# EEG_4.net
KiCad netlist of a schematic drawn in Altium Designer
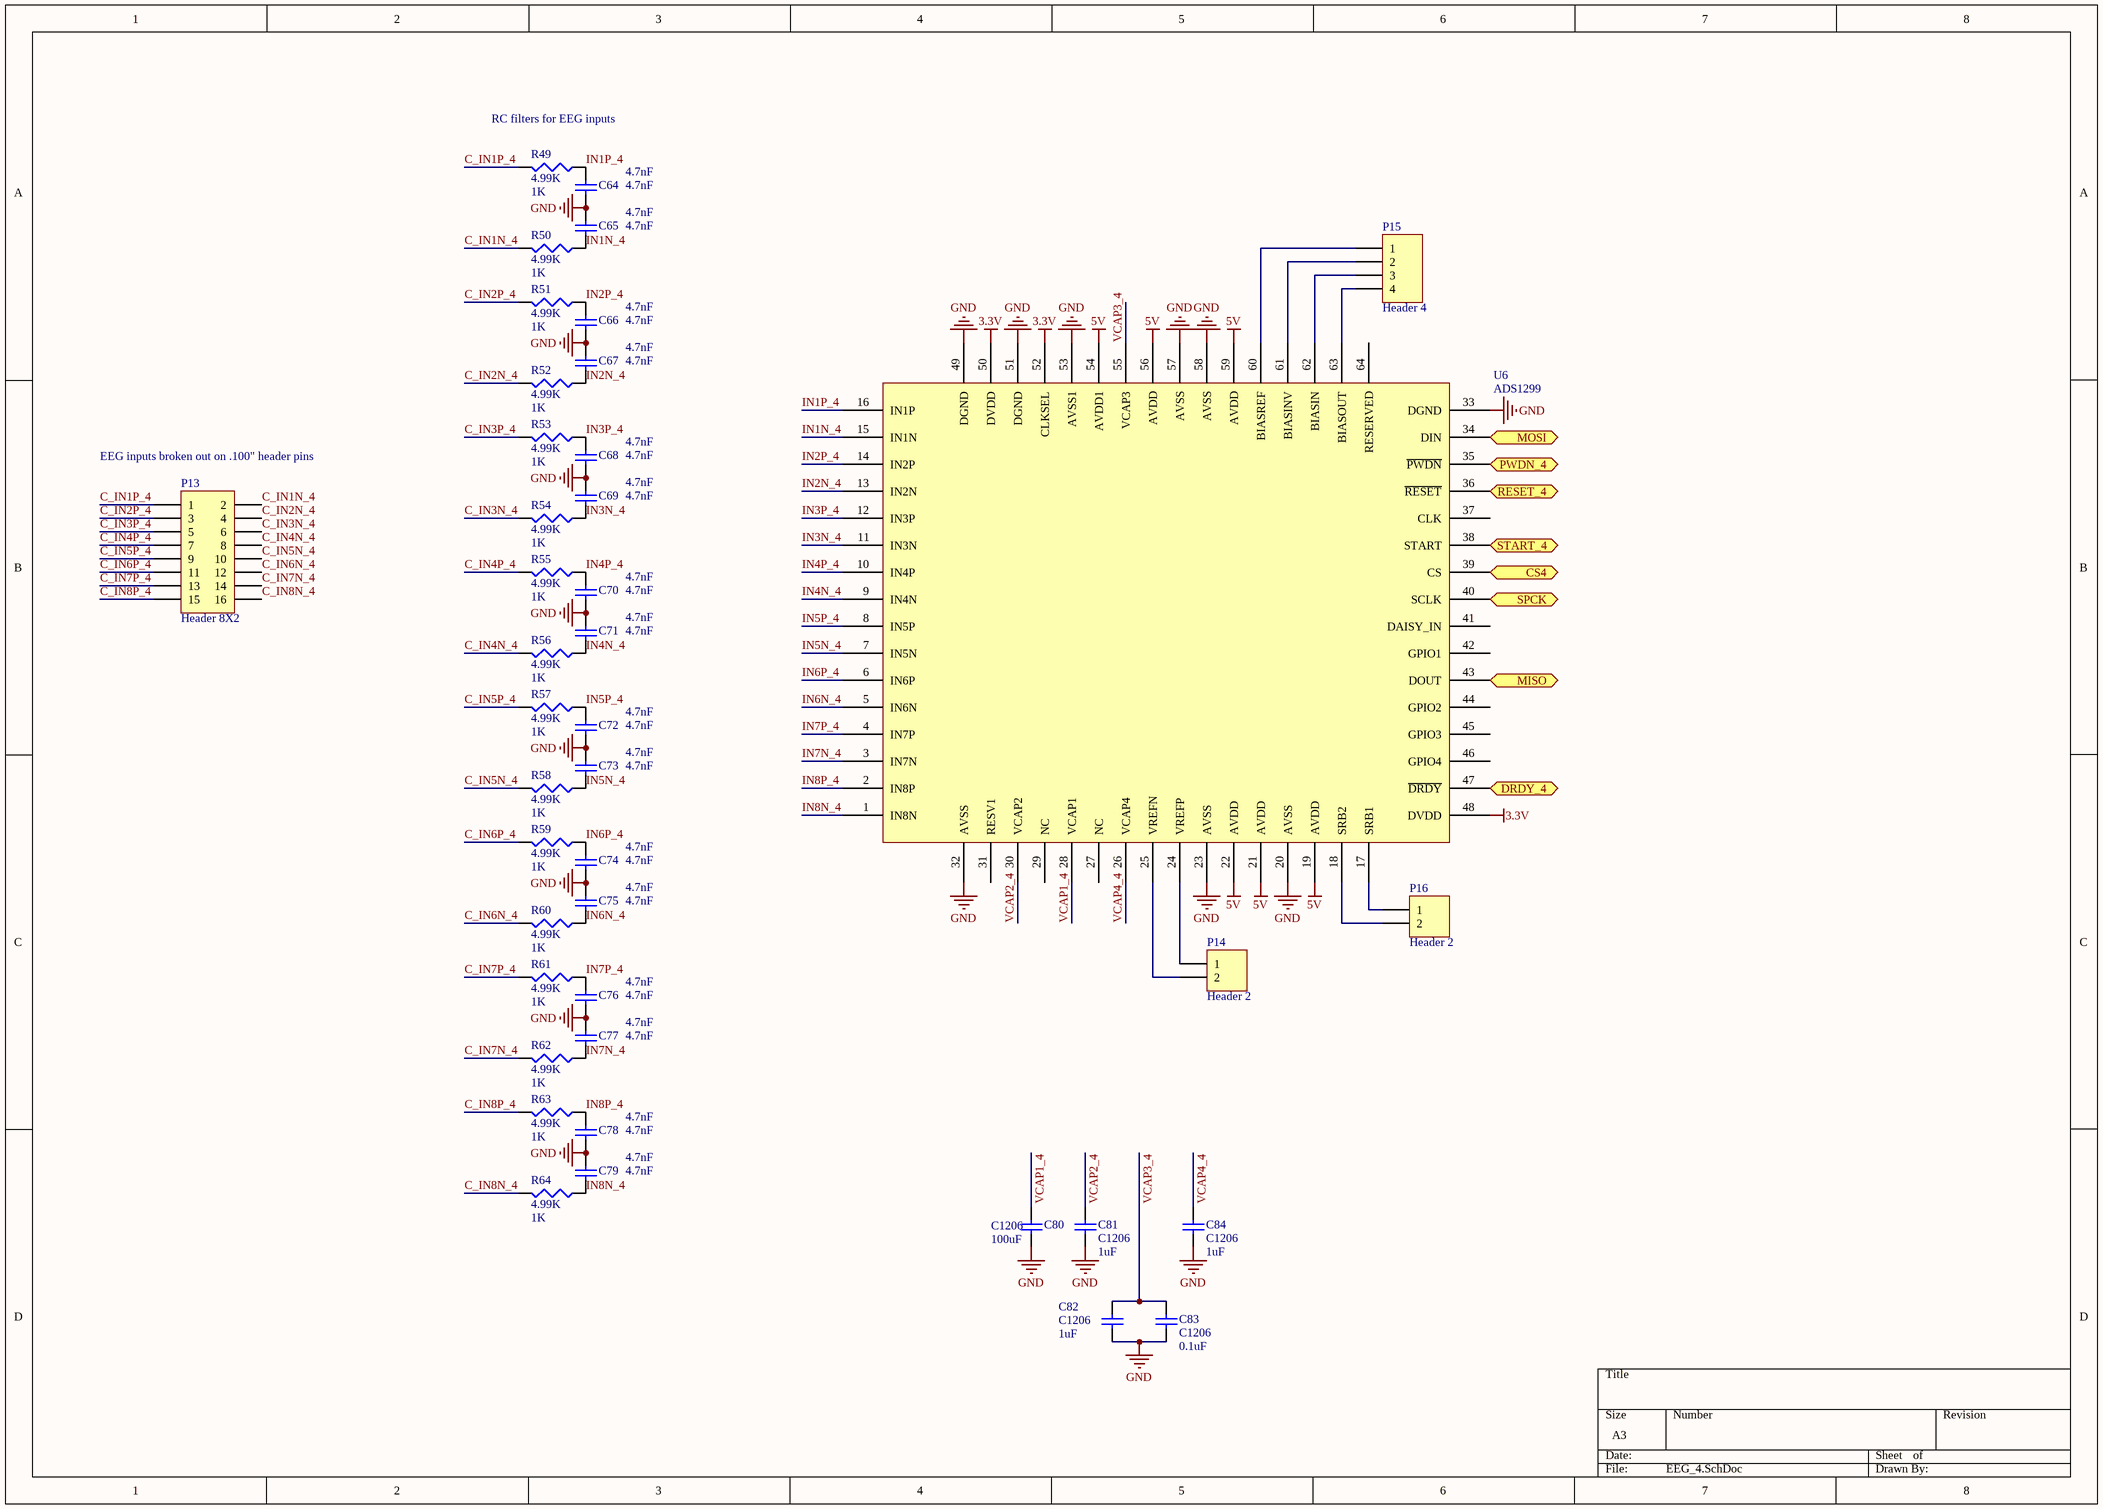
[diagram p0: EEG_4.SchDoc]

(export (version "E")
  (design (tool "Eeschema 10.0.6"))
  (components
    (comp (ref "C64")
      (value "4.7nF")
      (footprint "1608[0603]")
      (description "Capacitor (Semiconductor SIM Model)")
      (fields (field (name "ALTIUM_VALUE") "4.7nF") (field (name "PUBLISHER") "Altium Limited"))
      (libsource (lib "Miscellaneous Devices") (part "Cap Semi"))
    )
    (comp (ref "C65")
      (value "4.7nF")
      (footprint "1608[0603]")
      (description "Capacitor (Semiconductor SIM Model)")
      (fields (field (name "ALTIUM_VALUE") "4.7nF") (field (name "PUBLISHER") "Altium Limited"))
      (libsource (lib "Miscellaneous Devices") (part "Cap Semi"))
    )
    (comp (ref "C66")
      (value "4.7nF")
      (footprint "1608[0603]")
      (description "Capacitor (Semiconductor SIM Model)")
      (fields (field (name "ALTIUM_VALUE") "4.7nF") (field (name "PUBLISHER") "Altium Limited"))
      (libsource (lib "Miscellaneous Devices") (part "Cap Semi"))
    )
    (comp (ref "C67")
      (value "4.7nF")
      (footprint "1608[0603]")
      (description "Capacitor (Semiconductor SIM Model)")
      (fields (field (name "ALTIUM_VALUE") "4.7nF") (field (name "PUBLISHER") "Altium Limited"))
      (libsource (lib "Miscellaneous Devices") (part "Cap Semi"))
    )
    (comp (ref "C68")
      (value "4.7nF")
      (footprint "1608[0603]")
      (description "Capacitor (Semiconductor SIM Model)")
      (fields (field (name "ALTIUM_VALUE") "4.7nF") (field (name "PUBLISHER") "Altium Limited"))
      (libsource (lib "Miscellaneous Devices") (part "Cap Semi"))
    )
    (comp (ref "C69")
      (value "4.7nF")
      (footprint "1608[0603]")
      (description "Capacitor (Semiconductor SIM Model)")
      (fields (field (name "ALTIUM_VALUE") "4.7nF") (field (name "PUBLISHER") "Altium Limited"))
      (libsource (lib "Miscellaneous Devices") (part "Cap Semi"))
    )
    (comp (ref "C70")
      (value "4.7nF")
      (footprint "1608[0603]")
      (description "Capacitor (Semiconductor SIM Model)")
      (fields (field (name "ALTIUM_VALUE") "4.7nF") (field (name "PUBLISHER") "Altium Limited"))
      (libsource (lib "Miscellaneous Devices") (part "Cap Semi"))
    )
    (comp (ref "C71")
      (value "4.7nF")
      (footprint "1608[0603]")
      (description "Capacitor (Semiconductor SIM Model)")
      (fields (field (name "ALTIUM_VALUE") "4.7nF") (field (name "PUBLISHER") "Altium Limited"))
      (libsource (lib "Miscellaneous Devices") (part "Cap Semi"))
    )
    (comp (ref "C72")
      (value "4.7nF")
      (footprint "1608[0603]")
      (description "Capacitor (Semiconductor SIM Model)")
      (fields (field (name "ALTIUM_VALUE") "4.7nF") (field (name "PUBLISHER") "Altium Limited"))
      (libsource (lib "Miscellaneous Devices") (part "Cap Semi"))
    )
    (comp (ref "C73")
      (value "4.7nF")
      (footprint "1608[0603]")
      (description "Capacitor (Semiconductor SIM Model)")
      (fields (field (name "ALTIUM_VALUE") "4.7nF") (field (name "PUBLISHER") "Altium Limited"))
      (libsource (lib "Miscellaneous Devices") (part "Cap Semi"))
    )
    (comp (ref "C74")
      (value "4.7nF")
      (footprint "1608[0603]")
      (description "Capacitor (Semiconductor SIM Model)")
      (fields (field (name "ALTIUM_VALUE") "4.7nF") (field (name "PUBLISHER") "Altium Limited"))
      (libsource (lib "Miscellaneous Devices") (part "Cap Semi"))
    )
    (comp (ref "C75")
      (value "4.7nF")
      (footprint "1608[0603]")
      (description "Capacitor (Semiconductor SIM Model)")
      (fields (field (name "ALTIUM_VALUE") "4.7nF") (field (name "PUBLISHER") "Altium Limited"))
      (libsource (lib "Miscellaneous Devices") (part "Cap Semi"))
    )
    (comp (ref "C76")
      (value "4.7nF")
      (footprint "1608[0603]")
      (description "Capacitor (Semiconductor SIM Model)")
      (fields (field (name "ALTIUM_VALUE") "4.7nF") (field (name "PUBLISHER") "Altium Limited"))
      (libsource (lib "Miscellaneous Devices") (part "Cap Semi"))
    )
    (comp (ref "C77")
      (value "4.7nF")
      (footprint "1608[0603]")
      (description "Capacitor (Semiconductor SIM Model)")
      (fields (field (name "ALTIUM_VALUE") "4.7nF") (field (name "PUBLISHER") "Altium Limited"))
      (libsource (lib "Miscellaneous Devices") (part "Cap Semi"))
    )
    (comp (ref "C78")
      (value "4.7nF")
      (footprint "1608[0603]")
      (description "Capacitor (Semiconductor SIM Model)")
      (fields (field (name "ALTIUM_VALUE") "4.7nF") (field (name "PUBLISHER") "Altium Limited"))
      (libsource (lib "Miscellaneous Devices") (part "Cap Semi"))
    )
    (comp (ref "C79")
      (value "4.7nF")
      (footprint "1608[0603]")
      (description "Capacitor (Semiconductor SIM Model)")
      (fields (field (name "ALTIUM_VALUE") "4.7nF") (field (name "PUBLISHER") "Altium Limited"))
      (libsource (lib "Miscellaneous Devices") (part "Cap Semi"))
    )
    (comp (ref "C80")
      (value "C1206")
      (footprint "1608[0603]")
      (description "Capacitor (Semiconductor SIM Model)")
      (fields (field (name "ALTIUM_VALUE") "100uF") (field (name "PUBLISHER") "Altium Limited"))
      (libsource (lib "Miscellaneous Devices") (part "Cap Semi"))
    )
    (comp (ref "C81")
      (value "C1206")
      (footprint "1608[0603]")
      (description "Capacitor (Semiconductor SIM Model)")
      (fields (field (name "ALTIUM_VALUE") "1uF") (field (name "PUBLISHER") "Altium Limited"))
      (libsource (lib "Miscellaneous Devices") (part "Cap Semi"))
    )
    (comp (ref "C82")
      (value "C1206")
      (footprint "1608[0603]")
      (description "Capacitor (Semiconductor SIM Model)")
      (fields (field (name "ALTIUM_VALUE") "1uF") (field (name "PUBLISHER") "Altium Limited"))
      (libsource (lib "Miscellaneous Devices") (part "Cap Semi"))
    )
    (comp (ref "C83")
      (value "C1206")
      (footprint "1608[0603]")
      (description "Capacitor (Semiconductor SIM Model)")
      (fields (field (name "ALTIUM_VALUE") "0.1uF") (field (name "PUBLISHER") "Altium Limited"))
      (libsource (lib "Miscellaneous Devices") (part "Cap Semi"))
    )
    (comp (ref "C84")
      (value "C1206")
      (footprint "1608[0603]")
      (description "Capacitor (Semiconductor SIM Model)")
      (fields (field (name "ALTIUM_VALUE") "1uF") (field (name "PUBLISHER") "Altium Limited"))
      (libsource (lib "Miscellaneous Devices") (part "Cap Semi"))
    )
    (comp (ref "P13")
      (value "Header 8X2")
      (footprint "HDR2X8")
      (description "Header, 8-Pin, Dual row")
      (fields (field (name "PUBLISHER") "Altium Limited"))
      (libsource (lib "Miscellaneous Connectors") (part "Header 8X2"))
    )
    (comp (ref "P14")
      (value "Header 2")
      (footprint "HDR1X2")
      (description "Header, 2-Pin")
      (fields (field (name "PUBLISHER") "Altium Limited"))
      (libsource (lib "Miscellaneous Connectors") (part "Header 2"))
    )
    (comp (ref "P15")
      (value "Header 4")
      (footprint "HDR1X4")
      (description "Header, 4-Pin")
      (fields (field (name "PUBLISHER") "Altium Limited"))
      (libsource (lib "Miscellaneous Connectors") (part "Header 4"))
    )
    (comp (ref "P16")
      (value "Header 2")
      (footprint "HDR1X2")
      (description "Header, 2-Pin")
      (fields (field (name "PUBLISHER") "Altium Limited"))
      (libsource (lib "Miscellaneous Connectors") (part "Header 2"))
    )
    (comp (ref "R49")
      (value "4.99K")
      (footprint "1608[0603]")
      (description "Resistor")
      (fields (field (name "ALTIUM_VALUE") "1K") (field (name "PUBLISHER") "Altium Limited"))
      (libsource (lib "Miscellaneous Devices") (part "Res3"))
    )
    (comp (ref "R50")
      (value "4.99K")
      (footprint "1608[0603]")
      (description "Resistor")
      (fields (field (name "ALTIUM_VALUE") "1K") (field (name "PUBLISHER") "Altium Limited"))
      (libsource (lib "Miscellaneous Devices") (part "Res3"))
    )
    (comp (ref "R51")
      (value "4.99K")
      (footprint "1608[0603]")
      (description "Resistor")
      (fields (field (name "ALTIUM_VALUE") "1K") (field (name "PUBLISHER") "Altium Limited"))
      (libsource (lib "Miscellaneous Devices") (part "Res3"))
    )
    (comp (ref "R52")
      (value "4.99K")
      (footprint "1608[0603]")
      (description "Resistor")
      (fields (field (name "ALTIUM_VALUE") "1K") (field (name "PUBLISHER") "Altium Limited"))
      (libsource (lib "Miscellaneous Devices") (part "Res3"))
    )
    (comp (ref "R53")
      (value "4.99K")
      (footprint "1608[0603]")
      (description "Resistor")
      (fields (field (name "ALTIUM_VALUE") "1K") (field (name "PUBLISHER") "Altium Limited"))
      (libsource (lib "Miscellaneous Devices") (part "Res3"))
    )
    (comp (ref "R54")
      (value "4.99K")
      (footprint "1608[0603]")
      (description "Resistor")
      (fields (field (name "ALTIUM_VALUE") "1K") (field (name "PUBLISHER") "Altium Limited"))
      (libsource (lib "Miscellaneous Devices") (part "Res3"))
    )
    (comp (ref "R55")
      (value "4.99K")
      (footprint "1608[0603]")
      (description "Resistor")
      (fields (field (name "ALTIUM_VALUE") "1K") (field (name "PUBLISHER") "Altium Limited"))
      (libsource (lib "Miscellaneous Devices") (part "Res3"))
    )
    (comp (ref "R56")
      (value "4.99K")
      (footprint "1608[0603]")
      (description "Resistor")
      (fields (field (name "ALTIUM_VALUE") "1K") (field (name "PUBLISHER") "Altium Limited"))
      (libsource (lib "Miscellaneous Devices") (part "Res3"))
    )
    (comp (ref "R57")
      (value "4.99K")
      (footprint "1608[0603]")
      (description "Resistor")
      (fields (field (name "ALTIUM_VALUE") "1K") (field (name "PUBLISHER") "Altium Limited"))
      (libsource (lib "Miscellaneous Devices") (part "Res3"))
    )
    (comp (ref "R58")
      (value "4.99K")
      (footprint "1608[0603]")
      (description "Resistor")
      (fields (field (name "ALTIUM_VALUE") "1K") (field (name "PUBLISHER") "Altium Limited"))
      (libsource (lib "Miscellaneous Devices") (part "Res3"))
    )
    (comp (ref "R59")
      (value "4.99K")
      (footprint "1608[0603]")
      (description "Resistor")
      (fields (field (name "ALTIUM_VALUE") "1K") (field (name "PUBLISHER") "Altium Limited"))
      (libsource (lib "Miscellaneous Devices") (part "Res3"))
    )
    (comp (ref "R60")
      (value "4.99K")
      (footprint "1608[0603]")
      (description "Resistor")
      (fields (field (name "ALTIUM_VALUE") "1K") (field (name "PUBLISHER") "Altium Limited"))
      (libsource (lib "Miscellaneous Devices") (part "Res3"))
    )
    (comp (ref "R61")
      (value "4.99K")
      (footprint "1608[0603]")
      (description "Resistor")
      (fields (field (name "ALTIUM_VALUE") "1K") (field (name "PUBLISHER") "Altium Limited"))
      (libsource (lib "Miscellaneous Devices") (part "Res3"))
    )
    (comp (ref "R62")
      (value "4.99K")
      (footprint "1608[0603]")
      (description "Resistor")
      (fields (field (name "ALTIUM_VALUE") "1K") (field (name "PUBLISHER") "Altium Limited"))
      (libsource (lib "Miscellaneous Devices") (part "Res3"))
    )
    (comp (ref "R63")
      (value "4.99K")
      (footprint "1608[0603]")
      (description "Resistor")
      (fields (field (name "ALTIUM_VALUE") "1K") (field (name "PUBLISHER") "Altium Limited"))
      (libsource (lib "Miscellaneous Devices") (part "Res3"))
    )
    (comp (ref "R64")
      (value "4.99K")
      (footprint "1608[0603]")
      (description "Resistor")
      (fields (field (name "ALTIUM_VALUE") "1K") (field (name "PUBLISHER") "Altium Limited"))
      (libsource (lib "Miscellaneous Devices") (part "Res3"))
    )
    (comp (ref "U6")
      (value "ADS1299")
      (footprint "ADS1299 Plastic QFP")
      (libsource (lib "ADS1299") (part "ADS1299"))
    )
  )
  (nets
    (net (code "1") (name "/CS4") (class "Default")
      (node (ref "U6") (pin "39") (pinfunction "CS_39") (pintype "passive"))
    )
    (net (code "2") (name "/C_IN1N_4") (class "Default")
      (node (ref "P13") (pin "2") (pinfunction "2_2") (pintype "passive"))
      (node (ref "R50") (pin "2") (pinfunction "2_2") (pintype "passive"))
    )
    (net (code "3") (name "/C_IN1P_4") (class "Default")
      (node (ref "P13") (pin "1") (pinfunction "1_1") (pintype "passive"))
      (node (ref "R49") (pin "2") (pinfunction "2_2") (pintype "passive"))
    )
    (net (code "4") (name "/C_IN2N_4") (class "Default")
      (node (ref "P13") (pin "4") (pinfunction "4_4") (pintype "passive"))
      (node (ref "R52") (pin "2") (pinfunction "2_2") (pintype "passive"))
    )
    (net (code "5") (name "/C_IN2P_4") (class "Default")
      (node (ref "P13") (pin "3") (pinfunction "3_3") (pintype "passive"))
      (node (ref "R51") (pin "2") (pinfunction "2_2") (pintype "passive"))
    )
    (net (code "6") (name "/C_IN3N_4") (class "Default")
      (node (ref "P13") (pin "6") (pinfunction "6_6") (pintype "passive"))
      (node (ref "R54") (pin "2") (pinfunction "2_2") (pintype "passive"))
    )
    (net (code "7") (name "/C_IN3P_4") (class "Default")
      (node (ref "P13") (pin "5") (pinfunction "5_5") (pintype "passive"))
      (node (ref "R53") (pin "2") (pinfunction "2_2") (pintype "passive"))
    )
    (net (code "8") (name "/C_IN4N_4") (class "Default")
      (node (ref "P13") (pin "8") (pinfunction "8_8") (pintype "passive"))
      (node (ref "R56") (pin "2") (pinfunction "2_2") (pintype "passive"))
    )
    (net (code "9") (name "/C_IN4P_4") (class "Default")
      (node (ref "P13") (pin "7") (pinfunction "7_7") (pintype "passive"))
      (node (ref "R55") (pin "2") (pinfunction "2_2") (pintype "passive"))
    )
    (net (code "10") (name "/C_IN5N_4") (class "Default")
      (node (ref "P13") (pin "10") (pinfunction "10_10") (pintype "passive"))
      (node (ref "R58") (pin "2") (pinfunction "2_2") (pintype "passive"))
    )
    (net (code "11") (name "/C_IN5P_4") (class "Default")
      (node (ref "P13") (pin "9") (pinfunction "9_9") (pintype "passive"))
      (node (ref "R57") (pin "2") (pinfunction "2_2") (pintype "passive"))
    )
    (net (code "12") (name "/C_IN6N_4") (class "Default")
      (node (ref "P13") (pin "12") (pinfunction "12_12") (pintype "passive"))
      (node (ref "R60") (pin "2") (pinfunction "2_2") (pintype "passive"))
    )
    (net (code "13") (name "/C_IN6P_4") (class "Default")
      (node (ref "P13") (pin "11") (pinfunction "11_11") (pintype "passive"))
      (node (ref "R59") (pin "2") (pinfunction "2_2") (pintype "passive"))
    )
    (net (code "14") (name "/C_IN7N_4") (class "Default")
      (node (ref "P13") (pin "14") (pinfunction "14_14") (pintype "passive"))
      (node (ref "R62") (pin "2") (pinfunction "2_2") (pintype "passive"))
    )
    (net (code "15") (name "/C_IN7P_4") (class "Default")
      (node (ref "P13") (pin "13") (pinfunction "13_13") (pintype "passive"))
      (node (ref "R61") (pin "2") (pinfunction "2_2") (pintype "passive"))
    )
    (net (code "16") (name "/C_IN8N_4") (class "Default")
      (node (ref "P13") (pin "16") (pinfunction "16_16") (pintype "passive"))
      (node (ref "R64") (pin "2") (pinfunction "2_2") (pintype "passive"))
    )
    (net (code "17") (name "/C_IN8P_4") (class "Default")
      (node (ref "P13") (pin "15") (pinfunction "15_15") (pintype "passive"))
      (node (ref "R63") (pin "2") (pinfunction "2_2") (pintype "passive"))
    )
    (net (code "18") (name "/DRDY_4") (class "Default")
      (node (ref "U6") (pin "47") (pinfunction "~{DRDY}_47") (pintype "passive"))
    )
    (net (code "19") (name "/IN1N_4") (class "Default")
      (node (ref "C65") (pin "1") (pinfunction "1_1") (pintype "passive"))
      (node (ref "R50") (pin "1") (pinfunction "1_1") (pintype "passive"))
      (node (ref "U6") (pin "15") (pinfunction "IN1N_15") (pintype "passive"))
    )
    (net (code "20") (name "/IN1P_4") (class "Default")
      (node (ref "C64") (pin "2") (pinfunction "2_2") (pintype "passive"))
      (node (ref "R49") (pin "1") (pinfunction "1_1") (pintype "passive"))
      (node (ref "U6") (pin "16") (pinfunction "IN1P_16") (pintype "passive"))
    )
    (net (code "21") (name "/IN2N_4") (class "Default")
      (node (ref "C67") (pin "1") (pinfunction "1_1") (pintype "passive"))
      (node (ref "R52") (pin "1") (pinfunction "1_1") (pintype "passive"))
      (node (ref "U6") (pin "13") (pinfunction "IN2N_13") (pintype "passive"))
    )
    (net (code "22") (name "/IN2P_4") (class "Default")
      (node (ref "C66") (pin "2") (pinfunction "2_2") (pintype "passive"))
      (node (ref "R51") (pin "1") (pinfunction "1_1") (pintype "passive"))
      (node (ref "U6") (pin "14") (pinfunction "IN2P_14") (pintype "passive"))
    )
    (net (code "23") (name "/IN3N_4") (class "Default")
      (node (ref "C69") (pin "1") (pinfunction "1_1") (pintype "passive"))
      (node (ref "R54") (pin "1") (pinfunction "1_1") (pintype "passive"))
      (node (ref "U6") (pin "11") (pinfunction "IN3N_11") (pintype "passive"))
    )
    (net (code "24") (name "/IN3P_4") (class "Default")
      (node (ref "C68") (pin "2") (pinfunction "2_2") (pintype "passive"))
      (node (ref "R53") (pin "1") (pinfunction "1_1") (pintype "passive"))
      (node (ref "U6") (pin "12") (pinfunction "IN3P_12") (pintype "passive"))
    )
    (net (code "25") (name "/IN4N_4") (class "Default")
      (node (ref "C71") (pin "1") (pinfunction "1_1") (pintype "passive"))
      (node (ref "R56") (pin "1") (pinfunction "1_1") (pintype "passive"))
      (node (ref "U6") (pin "9") (pinfunction "IN4N_9") (pintype "passive"))
    )
    (net (code "26") (name "/IN4P_4") (class "Default")
      (node (ref "C70") (pin "2") (pinfunction "2_2") (pintype "passive"))
      (node (ref "R55") (pin "1") (pinfunction "1_1") (pintype "passive"))
      (node (ref "U6") (pin "10") (pinfunction "IN4P_10") (pintype "passive"))
    )
    (net (code "27") (name "/IN5N_4") (class "Default")
      (node (ref "C73") (pin "1") (pinfunction "1_1") (pintype "passive"))
      (node (ref "R58") (pin "1") (pinfunction "1_1") (pintype "passive"))
      (node (ref "U6") (pin "7") (pinfunction "IN5N_7") (pintype "passive"))
    )
    (net (code "28") (name "/IN5P_4") (class "Default")
      (node (ref "C72") (pin "2") (pinfunction "2_2") (pintype "passive"))
      (node (ref "R57") (pin "1") (pinfunction "1_1") (pintype "passive"))
      (node (ref "U6") (pin "8") (pinfunction "IN5P_8") (pintype "passive"))
    )
    (net (code "29") (name "/IN6N_4") (class "Default")
      (node (ref "C75") (pin "1") (pinfunction "1_1") (pintype "passive"))
      (node (ref "R60") (pin "1") (pinfunction "1_1") (pintype "passive"))
      (node (ref "U6") (pin "5") (pinfunction "IN6N_5") (pintype "passive"))
    )
    (net (code "30") (name "/IN6P_4") (class "Default")
      (node (ref "C74") (pin "2") (pinfunction "2_2") (pintype "passive"))
      (node (ref "R59") (pin "1") (pinfunction "1_1") (pintype "passive"))
      (node (ref "U6") (pin "6") (pinfunction "IN6P_6") (pintype "passive"))
    )
    (net (code "31") (name "/IN7N_4") (class "Default")
      (node (ref "C77") (pin "1") (pinfunction "1_1") (pintype "passive"))
      (node (ref "R62") (pin "1") (pinfunction "1_1") (pintype "passive"))
      (node (ref "U6") (pin "3") (pinfunction "IN7N_3") (pintype "passive"))
    )
    (net (code "32") (name "/IN7P_4") (class "Default")
      (node (ref "C76") (pin "2") (pinfunction "2_2") (pintype "passive"))
      (node (ref "R61") (pin "1") (pinfunction "1_1") (pintype "passive"))
      (node (ref "U6") (pin "4") (pinfunction "IN7P_4") (pintype "passive"))
    )
    (net (code "33") (name "/IN8N_4") (class "Default")
      (node (ref "C79") (pin "1") (pinfunction "1_1") (pintype "passive"))
      (node (ref "R64") (pin "1") (pinfunction "1_1") (pintype "passive"))
      (node (ref "U6") (pin "1") (pinfunction "IN8N_1") (pintype "passive"))
    )
    (net (code "34") (name "/IN8P_4") (class "Default")
      (node (ref "C78") (pin "2") (pinfunction "2_2") (pintype "passive"))
      (node (ref "R63") (pin "1") (pinfunction "1_1") (pintype "passive"))
      (node (ref "U6") (pin "2") (pinfunction "IN8P_2") (pintype "passive"))
    )
    (net (code "35") (name "/MISO") (class "Default")
      (node (ref "U6") (pin "43") (pinfunction "DOUT_43") (pintype "passive"))
    )
    (net (code "36") (name "/MOSI") (class "Default")
      (node (ref "U6") (pin "34") (pinfunction "DIN_34") (pintype "passive"))
    )
    (net (code "37") (name "/PWDN_4") (class "Default")
      (node (ref "U6") (pin "35") (pinfunction "~{PWDN}_35") (pintype "passive"))
    )
    (net (code "38") (name "/RESET_4") (class "Default")
      (node (ref "U6") (pin "36") (pinfunction "~{RESET}_36") (pintype "passive"))
    )
    (net (code "39") (name "/SPCK") (class "Default")
      (node (ref "U6") (pin "40") (pinfunction "SCLK_40") (pintype "passive"))
    )
    (net (code "40") (name "/START_4") (class "Default")
      (node (ref "U6") (pin "38") (pinfunction "START_38") (pintype "passive"))
    )
    (net (code "41") (name "/VCAP1_4") (class "Default")
      (node (ref "C80") (pin "1") (pinfunction "1_1") (pintype "passive"))
      (node (ref "U6") (pin "28") (pinfunction "VCAP1_28") (pintype "passive"))
    )
    (net (code "42") (name "/VCAP2_4") (class "Default")
      (node (ref "C81") (pin "2") (pinfunction "2_2") (pintype "passive"))
      (node (ref "U6") (pin "30") (pinfunction "VCAP2_30") (pintype "passive"))
    )
    (net (code "43") (name "/VCAP3_4") (class "Default")
      (node (ref "C82") (pin "1") (pinfunction "1_1") (pintype "passive"))
      (node (ref "C83") (pin "2") (pinfunction "2_2") (pintype "passive"))
      (node (ref "U6") (pin "55") (pinfunction "VCAP3_55") (pintype "passive"))
    )
    (net (code "44") (name "/VCAP4_4") (class "Default")
      (node (ref "C84") (pin "2") (pinfunction "2_2") (pintype "passive"))
      (node (ref "U6") (pin "26") (pinfunction "VCAP4_26") (pintype "passive"))
    )
    (net (code "45") (name "3.3V") (class "Default")
      (node (ref "U6") (pin "48") (pinfunction "DVDD_48") (pintype "passive"))
      (node (ref "U6") (pin "50") (pinfunction "DVDD_50") (pintype "passive"))
      (node (ref "U6") (pin "52") (pinfunction "CLKSEL_52") (pintype "passive"))
    )
    (net (code "46") (name "5V") (class "Default")
      (node (ref "U6") (pin "19") (pinfunction "AVDD_19") (pintype "passive"))
      (node (ref "U6") (pin "21") (pinfunction "AVDD_21") (pintype "passive"))
      (node (ref "U6") (pin "22") (pinfunction "AVDD_22") (pintype "passive"))
      (node (ref "U6") (pin "54") (pinfunction "AVDD1_54") (pintype "passive"))
      (node (ref "U6") (pin "56") (pinfunction "AVDD_56") (pintype "passive"))
      (node (ref "U6") (pin "59") (pinfunction "AVDD_59") (pintype "passive"))
    )
    (net (code "47") (name "GND") (class "Default")
      (node (ref "C64") (pin "1") (pinfunction "1_1") (pintype "passive"))
      (node (ref "C65") (pin "2") (pinfunction "2_2") (pintype "passive"))
      (node (ref "C66") (pin "1") (pinfunction "1_1") (pintype "passive"))
      (node (ref "C67") (pin "2") (pinfunction "2_2") (pintype "passive"))
      (node (ref "C68") (pin "1") (pinfunction "1_1") (pintype "passive"))
      (node (ref "C69") (pin "2") (pinfunction "2_2") (pintype "passive"))
      (node (ref "C70") (pin "1") (pinfunction "1_1") (pintype "passive"))
      (node (ref "C71") (pin "2") (pinfunction "2_2") (pintype "passive"))
      (node (ref "C72") (pin "1") (pinfunction "1_1") (pintype "passive"))
      (node (ref "C73") (pin "2") (pinfunction "2_2") (pintype "passive"))
      (node (ref "C74") (pin "1") (pinfunction "1_1") (pintype "passive"))
      (node (ref "C75") (pin "2") (pinfunction "2_2") (pintype "passive"))
      (node (ref "C76") (pin "1") (pinfunction "1_1") (pintype "passive"))
      (node (ref "C77") (pin "2") (pinfunction "2_2") (pintype "passive"))
      (node (ref "C78") (pin "1") (pinfunction "1_1") (pintype "passive"))
      (node (ref "C79") (pin "2") (pinfunction "2_2") (pintype "passive"))
      (node (ref "C80") (pin "2") (pinfunction "2_2") (pintype "passive"))
      (node (ref "C81") (pin "1") (pinfunction "1_1") (pintype "passive"))
      (node (ref "C82") (pin "2") (pinfunction "2_2") (pintype "passive"))
      (node (ref "C83") (pin "1") (pinfunction "1_1") (pintype "passive"))
      (node (ref "C84") (pin "1") (pinfunction "1_1") (pintype "passive"))
      (node (ref "U6") (pin "20") (pinfunction "AVSS_20") (pintype "passive"))
      (node (ref "U6") (pin "23") (pinfunction "AVSS_23") (pintype "passive"))
      (node (ref "U6") (pin "32") (pinfunction "AVSS_32") (pintype "passive"))
      (node (ref "U6") (pin "33") (pinfunction "DGND_33") (pintype "passive"))
      (node (ref "U6") (pin "49") (pinfunction "DGND_49") (pintype "passive"))
      (node (ref "U6") (pin "51") (pinfunction "DGND_51") (pintype "passive"))
      (node (ref "U6") (pin "53") (pinfunction "AVSS1_53") (pintype "passive"))
      (node (ref "U6") (pin "57") (pinfunction "AVSS_57") (pintype "passive"))
      (node (ref "U6") (pin "58") (pinfunction "AVSS_58") (pintype "passive"))
    )
    (net (code "48") (name "Net-(U6-BIASIN)") (class "Default")
      (node (ref "P15") (pin "3") (pinfunction "3_3") (pintype "passive"))
      (node (ref "U6") (pin "62") (pinfunction "BIASIN_62") (pintype "passive"))
    )
    (net (code "49") (name "Net-(U6-BIASINV)") (class "Default")
      (node (ref "P15") (pin "2") (pinfunction "2_2") (pintype "passive"))
      (node (ref "U6") (pin "61") (pinfunction "BIASINV_61") (pintype "passive"))
    )
    (net (code "50") (name "Net-(U6-BIASOUT)") (class "Default")
      (node (ref "P15") (pin "4") (pinfunction "4_4") (pintype "passive"))
      (node (ref "U6") (pin "63") (pinfunction "BIASOUT_63") (pintype "passive"))
    )
    (net (code "51") (name "Net-(U6-BIASREF)") (class "Default")
      (node (ref "P15") (pin "1") (pinfunction "1_1") (pintype "passive"))
      (node (ref "U6") (pin "60") (pinfunction "BIASREF_60") (pintype "passive"))
    )
    (net (code "52") (name "Net-(U6-SRB1)") (class "Default")
      (node (ref "P16") (pin "1") (pinfunction "1_1") (pintype "passive"))
      (node (ref "U6") (pin "17") (pinfunction "SRB1_17") (pintype "passive"))
    )
    (net (code "53") (name "Net-(U6-SRB2)") (class "Default")
      (node (ref "P16") (pin "2") (pinfunction "2_2") (pintype "passive"))
      (node (ref "U6") (pin "18") (pinfunction "SRB2_18") (pintype "passive"))
    )
    (net (code "54") (name "Net-(U6-VREFN)") (class "Default")
      (node (ref "P14") (pin "2") (pinfunction "2_2") (pintype "passive"))
      (node (ref "U6") (pin "25") (pinfunction "VREFN_25") (pintype "passive"))
    )
    (net (code "55") (name "Net-(U6-VREFP)") (class "Default")
      (node (ref "P14") (pin "1") (pinfunction "1_1") (pintype "passive"))
      (node (ref "U6") (pin "24") (pinfunction "VREFP_24") (pintype "passive"))
    )
    (net (code "56") (name "unconnected-(U6-CLK-Pad37)") (class "Default")
      (node (ref "U6") (pin "37") (pinfunction "CLK_37") (pintype "passive"))
    )
    (net (code "57") (name "unconnected-(U6-DAISY_IN-Pad41)") (class "Default")
      (node (ref "U6") (pin "41") (pinfunction "DAISY_IN_41") (pintype "passive"))
    )
    (net (code "58") (name "unconnected-(U6-GPIO1-Pad42)") (class "Default")
      (node (ref "U6") (pin "42") (pinfunction "GPIO1_42") (pintype "passive"))
    )
    (net (code "59") (name "unconnected-(U6-GPIO2-Pad44)") (class "Default")
      (node (ref "U6") (pin "44") (pinfunction "GPIO2_44") (pintype "passive"))
    )
    (net (code "60") (name "unconnected-(U6-GPIO3-Pad45)") (class "Default")
      (node (ref "U6") (pin "45") (pinfunction "GPIO3_45") (pintype "passive"))
    )
    (net (code "61") (name "unconnected-(U6-GPIO4-Pad46)") (class "Default")
      (node (ref "U6") (pin "46") (pinfunction "GPIO4_46") (pintype "passive"))
    )
    (net (code "62") (name "unconnected-(U6-NC-Pad27)") (class "Default")
      (node (ref "U6") (pin "27") (pinfunction "NC_27") (pintype "passive"))
    )
    (net (code "63") (name "unconnected-(U6-NC-Pad29)") (class "Default")
      (node (ref "U6") (pin "29") (pinfunction "NC_29") (pintype "passive"))
    )
    (net (code "64") (name "unconnected-(U6-RESERVED-Pad64)") (class "Default")
      (node (ref "U6") (pin "64") (pinfunction "RESERVED_64") (pintype "passive"))
    )
    (net (code "65") (name "unconnected-(U6-RESV1-Pad31)") (class "Default")
      (node (ref "U6") (pin "31") (pinfunction "RESV1_31") (pintype "passive"))
    )
  )
)
